# PCIe-SATA.net
KiCad netlist of a schematic drawn in Altium Designer
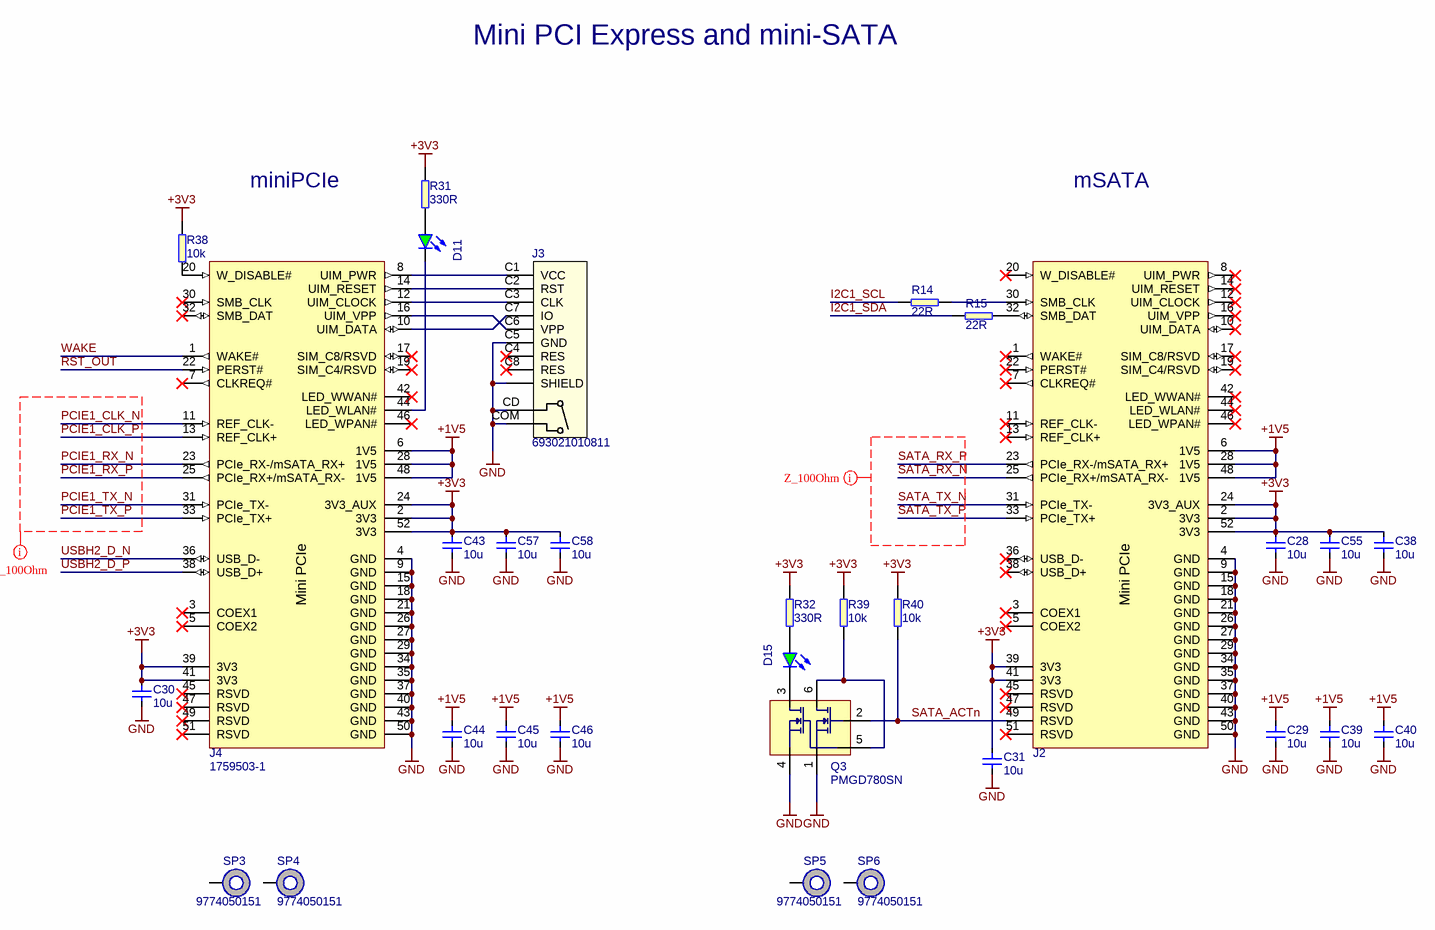
[diagram p0: PCIe-SATA.SchDoc]

(export (version "E")
  (design (tool "Eeschema 10.0.6"))
  (components
    (comp (ref "C28")
      (value "10u")
      (footprint "0603")
      (description "MLCC SMT Capacitor 10uF 0603")
      (fields (field (name "MANUFACTURER") "Walsin") (field (name "PART NUMBER") "C_10u_0603"))
      (libsource (lib "TK1Baseboard") (part "C_10u_0603"))
    )
    (comp (ref "C29")
      (value "10u")
      (footprint "0603")
      (description "MLCC SMT Capacitor 10uF 0603")
      (fields (field (name "MANUFACTURER") "Walsin") (field (name "PART NUMBER") "C_10u_0603"))
      (libsource (lib "TK1Baseboard") (part "C_10u_0603"))
    )
    (comp (ref "C30")
      (value "10u")
      (footprint "0603")
      (description "MLCC SMT Capacitor 10uF 0603")
      (fields (field (name "MANUFACTURER") "Walsin") (field (name "PART NUMBER") "C_10u_0603"))
      (libsource (lib "TK1Baseboard") (part "C_10u_0603"))
    )
    (comp (ref "C31")
      (value "10u")
      (footprint "0603")
      (description "MLCC SMT Capacitor 10uF 0603")
      (fields (field (name "MANUFACTURER") "Walsin") (field (name "PART NUMBER") "C_10u_0603"))
      (libsource (lib "TK1Baseboard") (part "C_10u_0603"))
    )
    (comp (ref "C38")
      (value "10u")
      (footprint "0603")
      (description "MLCC SMT Capacitor 10uF 0603")
      (fields (field (name "MANUFACTURER") "Walsin") (field (name "PART NUMBER") "C_10u_0603"))
      (libsource (lib "TK1Baseboard") (part "C_10u_0603"))
    )
    (comp (ref "C39")
      (value "10u")
      (footprint "0603")
      (description "MLCC SMT Capacitor 10uF 0603")
      (fields (field (name "MANUFACTURER") "Walsin") (field (name "PART NUMBER") "C_10u_0603"))
      (libsource (lib "TK1Baseboard") (part "C_10u_0603"))
    )
    (comp (ref "C40")
      (value "10u")
      (footprint "0603")
      (description "MLCC SMT Capacitor 10uF 0603")
      (fields (field (name "MANUFACTURER") "Walsin") (field (name "PART NUMBER") "C_10u_0603"))
      (libsource (lib "TK1Baseboard") (part "C_10u_0603"))
    )
    (comp (ref "C43")
      (value "10u")
      (footprint "0603")
      (description "MLCC SMT Capacitor 10uF 0603")
      (fields (field (name "MANUFACTURER") "Walsin") (field (name "PART NUMBER") "C_10u_0603"))
      (libsource (lib "TK1Baseboard") (part "C_10u_0603"))
    )
    (comp (ref "C44")
      (value "10u")
      (footprint "0603")
      (description "MLCC SMT Capacitor 10uF 0603")
      (fields (field (name "MANUFACTURER") "Walsin") (field (name "PART NUMBER") "C_10u_0603"))
      (libsource (lib "TK1Baseboard") (part "C_10u_0603"))
    )
    (comp (ref "C45")
      (value "10u")
      (footprint "0603")
      (description "MLCC SMT Capacitor 10uF 0603")
      (fields (field (name "MANUFACTURER") "Walsin") (field (name "PART NUMBER") "C_10u_0603"))
      (libsource (lib "TK1Baseboard") (part "C_10u_0603"))
    )
    (comp (ref "C46")
      (value "10u")
      (footprint "0603")
      (description "MLCC SMT Capacitor 10uF 0603")
      (fields (field (name "MANUFACTURER") "Walsin") (field (name "PART NUMBER") "C_10u_0603"))
      (libsource (lib "TK1Baseboard") (part "C_10u_0603"))
    )
    (comp (ref "C55")
      (value "10u")
      (footprint "0603")
      (description "MLCC SMT Capacitor 10uF 0603")
      (fields (field (name "MANUFACTURER") "Walsin") (field (name "PART NUMBER") "C_10u_0603"))
      (libsource (lib "TK1Baseboard") (part "C_10u_0603"))
    )
    (comp (ref "C57")
      (value "10u")
      (footprint "0603")
      (description "MLCC SMT Capacitor 10uF 0603")
      (fields (field (name "MANUFACTURER") "Walsin") (field (name "PART NUMBER") "C_10u_0603"))
      (libsource (lib "TK1Baseboard") (part "C_10u_0603"))
    )
    (comp (ref "C58")
      (value "10u")
      (footprint "0603")
      (description "MLCC SMT Capacitor 10uF 0603")
      (fields (field (name "MANUFACTURER") "Walsin") (field (name "PART NUMBER") "C_10u_0603"))
      (libsource (lib "TK1Baseboard") (part "C_10u_0603"))
    )
    (comp (ref "D11")
      (value "KPT-1608SGC")
      (footprint "LED0603")
      (description "LED Green 0603 case")
      (fields (field (name "PART NUMBER") "LED_G") (field (name "MANUFACTURER") "KINGBRIGHT"))
      (libsource (lib "TK1Baseboard") (part "LED_G"))
    )
    (comp (ref "D15")
      (value "KPT-1608SGC")
      (footprint "LED0603")
      (description "LED Green 0603 case")
      (fields (field (name "PART NUMBER") "LED_G") (field (name "MANUFACTURER") "KINGBRIGHT"))
      (libsource (lib "TK1Baseboard") (part "LED_G"))
    )
    (comp (ref "J2")
      (value "1759503-1")
      (footprint "1759503-1")
      (description "Mini PCI Express 8mm")
      (fields (field (name "PART NUMBER") "TE-1759503-1") (field (name "MANUFACTURER") "TE CONNECTIVITY"))
      (libsource (lib "TK1Baseboard") (part "MiniPCIExpress"))
    )
    (comp (ref "J3")
      (value "693021010811")
      (footprint "693021010811")
      (description "Micro SIM Card Connector WR-CRD, Push & Push - with Card Detection")
      (fields
        (field (name "MANUFACTURER") "WURTH ELEKTRONIK")
        (field (name "PART NUMBER") "WE-693-021-010-811")
      )
      (libsource (lib "TK1Baseboard") (part "SIM-8P-CD"))
    )
    (comp (ref "J4")
      (value "1759503-1")
      (footprint "1759503-1")
      (description "Mini PCI Express 8mm")
      (fields (field (name "PART NUMBER") "TE-1759503-1") (field (name "MANUFACTURER") "TE CONNECTIVITY"))
      (libsource (lib "TK1Baseboard") (part "MiniPCIExpress"))
    )
    (comp (ref "Q3")
      (value "PMGD780SN")
      (footprint "SOT-363")
      (description "60 V, dual N-channel Trench MOSFET")
      (fields (field (name "MANUFACTURER") "NXP") (field (name "MPN") "PMGD780SN,115"))
      (libsource (lib "TK1Baseboard") (part "PMGD780SN"))
    )
    (comp (ref "R14")
      (value "22R")
      (footprint "0402")
      (description "RES, 22R, 0402")
      (fields (field (name "MANUFACTURER") "VISHAY") (field (name "PART NUMBER") "R_22R_0402"))
      (libsource (lib "TK1Baseboard") (part "R_22R_0402"))
    )
    (comp (ref "R15")
      (value "22R")
      (footprint "0402")
      (description "RES, 22R, 0402")
      (fields (field (name "MANUFACTURER") "VISHAY") (field (name "PART NUMBER") "R_22R_0402"))
      (libsource (lib "TK1Baseboard") (part "R_22R_0402"))
    )
    (comp (ref "R31")
      (value "330R")
      (footprint "0402")
      (description "RES, 330R, 0402")
      (fields (field (name "MANUFACTURER") "MULTICOMP") (field (name "PART NUMBER") "R_330R_0402"))
      (libsource (lib "TK1Baseboard") (part "R_330R_0402"))
    )
    (comp (ref "R32")
      (value "330R")
      (footprint "0402")
      (description "RES, 330R, 0402")
      (fields (field (name "MANUFACTURER") "MULTICOMP") (field (name "PART NUMBER") "R_330R_0402"))
      (libsource (lib "TK1Baseboard") (part "R_330R_0402"))
    )
    (comp (ref "R38")
      (value "10k")
      (footprint "0402")
      (description "RES, 10k, 0402")
      (fields (field (name "MANUFACTURER") "MULTICOMP") (field (name "PART NUMBER") "R_10k_0402"))
      (libsource (lib "TK1Baseboard") (part "R_10k_0402"))
    )
    (comp (ref "R39")
      (value "10k")
      (footprint "0402")
      (description "RES, 10k, 0402")
      (fields (field (name "MANUFACTURER") "MULTICOMP") (field (name "PART NUMBER") "R_10k_0402"))
      (libsource (lib "TK1Baseboard") (part "R_10k_0402"))
    )
    (comp (ref "R40")
      (value "10k")
      (footprint "0402")
      (description "RES, 10k, 0402")
      (fields (field (name "MANUFACTURER") "MULTICOMP") (field (name "PART NUMBER") "R_10k_0402"))
      (libsource (lib "TK1Baseboard") (part "R_10k_0402"))
    )
    (comp (ref "SP3")
      (value "9774050151")
      (footprint "M2.5-5mm")
      (description "M2.5x5")
      (fields (field (name "MANUFACTURER") "WURTH ELEKTRONIK"))
      (libsource (lib "TK1Baseboard") (part "M2.5x5"))
    )
    (comp (ref "SP4")
      (value "9774050151")
      (footprint "M2.5-5mm")
      (description "M2.5x5")
      (fields (field (name "MANUFACTURER") "WURTH ELEKTRONIK"))
      (libsource (lib "TK1Baseboard") (part "M2.5x5"))
    )
    (comp (ref "SP5")
      (value "9774050151")
      (footprint "M2.5-5mm")
      (description "M2.5x5")
      (fields (field (name "MANUFACTURER") "WURTH ELEKTRONIK"))
      (libsource (lib "TK1Baseboard") (part "M2.5x5"))
    )
    (comp (ref "SP6")
      (value "9774050151")
      (footprint "M2.5-5mm")
      (description "M2.5x5")
      (fields (field (name "MANUFACTURER") "WURTH ELEKTRONIK"))
      (libsource (lib "TK1Baseboard") (part "M2.5x5"))
    )
  )
  (nets
    (net (code "1") (name "+1V5") (class "Default")
      (node (ref "C29") (pin "1") (pinfunction "1_1") (pintype "passive"))
      (node (ref "C39") (pin "1") (pinfunction "1_1") (pintype "passive"))
      (node (ref "C40") (pin "1") (pinfunction "1_1") (pintype "passive"))
      (node (ref "C44") (pin "1") (pinfunction "1_1") (pintype "passive"))
      (node (ref "C45") (pin "1") (pinfunction "1_1") (pintype "passive"))
      (node (ref "C46") (pin "1") (pinfunction "1_1") (pintype "passive"))
      (node (ref "J2") (pin "28") (pinfunction "1V5_28") (pintype "power_in"))
      (node (ref "J2") (pin "48") (pinfunction "1V5_48") (pintype "power_in"))
      (node (ref "J2") (pin "6") (pinfunction "1V5_6") (pintype "power_in"))
      (node (ref "J4") (pin "28") (pinfunction "1V5_28") (pintype "power_in"))
      (node (ref "J4") (pin "48") (pinfunction "1V5_48") (pintype "power_in"))
      (node (ref "J4") (pin "6") (pinfunction "1V5_6") (pintype "power_in"))
    )
    (net (code "2") (name "+3V3") (class "Default")
      (node (ref "C28") (pin "1") (pinfunction "1_1") (pintype "passive"))
      (node (ref "C30") (pin "1") (pinfunction "1_1") (pintype "passive"))
      (node (ref "C31") (pin "1") (pinfunction "1_1") (pintype "passive"))
      (node (ref "C38") (pin "1") (pinfunction "1_1") (pintype "passive"))
      (node (ref "C43") (pin "1") (pinfunction "1_1") (pintype "passive"))
      (node (ref "C55") (pin "1") (pinfunction "1_1") (pintype "passive"))
      (node (ref "C57") (pin "1") (pinfunction "1_1") (pintype "passive"))
      (node (ref "C58") (pin "1") (pinfunction "1_1") (pintype "passive"))
      (node (ref "J2") (pin "2") (pinfunction "3V3_2") (pintype "power_in"))
      (node (ref "J2") (pin "24") (pinfunction "3V3_AUX_24") (pintype "power_in"))
      (node (ref "J2") (pin "39") (pinfunction "3V3_39") (pintype "passive"))
      (node (ref "J2") (pin "41") (pinfunction "3V3_41") (pintype "passive"))
      (node (ref "J2") (pin "52") (pinfunction "3V3_52") (pintype "power_in"))
      (node (ref "J4") (pin "2") (pinfunction "3V3_2") (pintype "power_in"))
      (node (ref "J4") (pin "24") (pinfunction "3V3_AUX_24") (pintype "power_in"))
      (node (ref "J4") (pin "39") (pinfunction "3V3_39") (pintype "passive"))
      (node (ref "J4") (pin "41") (pinfunction "3V3_41") (pintype "passive"))
      (node (ref "J4") (pin "52") (pinfunction "3V3_52") (pintype "power_in"))
      (node (ref "R31") (pin "2") (pintype "passive"))
      (node (ref "R32") (pin "2") (pintype "passive"))
      (node (ref "R38") (pin "2") (pintype "passive"))
      (node (ref "R39") (pin "2") (pintype "passive"))
      (node (ref "R40") (pin "2") (pintype "passive"))
    )
    (net (code "3") (name "/I2C1_SCL") (class "Default") (node (ref "R14") (pin "1") (pintype "passive")))
    (net (code "4") (name "/I2C1_SDA") (class "Default") (node (ref "R15") (pin "1") (pintype "passive")))
    (net (code "5") (name "/PCIE1_CLK_N") (class "Default")
      (node (ref "J4") (pin "11") (pinfunction "REF_CLK-_11") (pintype "input"))
    )
    (net (code "6") (name "/PCIE1_CLK_P") (class "Default")
      (node (ref "J4") (pin "13") (pinfunction "REF_CLK+_13") (pintype "input"))
    )
    (net (code "7") (name "/PCIE1_RX_N") (class "Default")
      (node (ref "J4") (pin "23") (pinfunction "PCIe_RX-/mSATA_RX+_23") (pintype "output"))
    )
    (net (code "8") (name "/PCIE1_RX_P") (class "Default")
      (node (ref "J4") (pin "25") (pinfunction "PCIe_RX+/mSATA_RX-_25") (pintype "output"))
    )
    (net (code "9") (name "/PCIE1_TX_N") (class "Default")
      (node (ref "J4") (pin "31") (pinfunction "PCIe_TX-_31") (pintype "input"))
    )
    (net (code "10") (name "/PCIE1_TX_P") (class "Default")
      (node (ref "J4") (pin "33") (pinfunction "PCIe_TX+_33") (pintype "input"))
    )
    (net (code "11") (name "/RST_OUT") (class "Default")
      (node (ref "J4") (pin "22") (pinfunction "PERST#_22") (pintype "input"))
    )
    (net (code "12") (name "/SATA_ACTn") (class "Default")
      (node (ref "J2") (pin "49") (pinfunction "RSVD_49") (pintype "passive"))
      (node (ref "Q3") (pin "2") (pinfunction "G1_2") (pintype "passive"))
      (node (ref "R40") (pin "1") (pintype "passive"))
    )
    (net (code "13") (name "/SATA_RX_N") (class "Default")
      (node (ref "J2") (pin "25") (pinfunction "PCIe_RX+/mSATA_RX-_25") (pintype "output"))
    )
    (net (code "14") (name "/SATA_RX_P") (class "Default")
      (node (ref "J2") (pin "23") (pinfunction "PCIe_RX-/mSATA_RX+_23") (pintype "output"))
    )
    (net (code "15") (name "/SATA_TX_N") (class "Default")
      (node (ref "J2") (pin "31") (pinfunction "PCIe_TX-_31") (pintype "input"))
    )
    (net (code "16") (name "/SATA_TX_P") (class "Default")
      (node (ref "J2") (pin "33") (pinfunction "PCIe_TX+_33") (pintype "input"))
    )
    (net (code "17") (name "/USBH2_D_N") (class "Default")
      (node (ref "J4") (pin "36") (pinfunction "USB_D-_36") (pintype "bidirectional"))
    )
    (net (code "18") (name "/USBH2_D_P") (class "Default")
      (node (ref "J4") (pin "38") (pinfunction "USB_D+_38") (pintype "bidirectional"))
    )
    (net (code "19") (name "/WAKE") (class "Default")
      (node (ref "J4") (pin "1") (pinfunction "WAKE#_1") (pintype "output"))
    )
    (net (code "20") (name "GND") (class "Default")
      (node (ref "C28") (pin "2") (pinfunction "2_2") (pintype "passive"))
      (node (ref "C29") (pin "2") (pinfunction "2_2") (pintype "passive"))
      (node (ref "C30") (pin "2") (pinfunction "2_2") (pintype "passive"))
      (node (ref "C31") (pin "2") (pinfunction "2_2") (pintype "passive"))
      (node (ref "C38") (pin "2") (pinfunction "2_2") (pintype "passive"))
      (node (ref "C39") (pin "2") (pinfunction "2_2") (pintype "passive"))
      (node (ref "C40") (pin "2") (pinfunction "2_2") (pintype "passive"))
      (node (ref "C43") (pin "2") (pinfunction "2_2") (pintype "passive"))
      (node (ref "C44") (pin "2") (pinfunction "2_2") (pintype "passive"))
      (node (ref "C45") (pin "2") (pinfunction "2_2") (pintype "passive"))
      (node (ref "C46") (pin "2") (pinfunction "2_2") (pintype "passive"))
      (node (ref "C55") (pin "2") (pinfunction "2_2") (pintype "passive"))
      (node (ref "C57") (pin "2") (pinfunction "2_2") (pintype "passive"))
      (node (ref "C58") (pin "2") (pinfunction "2_2") (pintype "passive"))
      (node (ref "J2") (pin "15") (pinfunction "GND_15") (pintype "power_in"))
      (node (ref "J2") (pin "18") (pinfunction "GND_18") (pintype "power_in"))
      (node (ref "J2") (pin "21") (pinfunction "GND_21") (pintype "power_in"))
      (node (ref "J2") (pin "26") (pinfunction "GND_26") (pintype "power_in"))
      (node (ref "J2") (pin "27") (pinfunction "GND_27") (pintype "power_in"))
      (node (ref "J2") (pin "29") (pinfunction "GND_29") (pintype "power_in"))
      (node (ref "J2") (pin "34") (pinfunction "GND_34") (pintype "power_in"))
      (node (ref "J2") (pin "35") (pinfunction "GND_35") (pintype "power_in"))
      (node (ref "J2") (pin "37") (pinfunction "GND_37") (pintype "power_in"))
      (node (ref "J2") (pin "4") (pinfunction "GND_4") (pintype "power_in"))
      (node (ref "J2") (pin "40") (pinfunction "GND_40") (pintype "power_in"))
      (node (ref "J2") (pin "43") (pinfunction "GND_43") (pintype "power_in"))
      (node (ref "J2") (pin "50") (pinfunction "GND_50") (pintype "power_in"))
      (node (ref "J2") (pin "9") (pinfunction "GND_9") (pintype "power_in"))
      (node (ref "J3") (pin "C5") (pinfunction "GND_C5") (pintype "passive"))
      (node (ref "J3") (pin "CD") (pinfunction "CD_CD") (pintype "passive"))
      (node (ref "J3") (pin "COM") (pinfunction "COM_COM") (pintype "passive"))
      (node (ref "J3") (pin "SHIELD") (pinfunction "SHIELD_SHIELD") (pintype "passive"))
      (node (ref "J4") (pin "15") (pinfunction "GND_15") (pintype "power_in"))
      (node (ref "J4") (pin "18") (pinfunction "GND_18") (pintype "power_in"))
      (node (ref "J4") (pin "21") (pinfunction "GND_21") (pintype "power_in"))
      (node (ref "J4") (pin "26") (pinfunction "GND_26") (pintype "power_in"))
      (node (ref "J4") (pin "27") (pinfunction "GND_27") (pintype "power_in"))
      (node (ref "J4") (pin "29") (pinfunction "GND_29") (pintype "power_in"))
      (node (ref "J4") (pin "34") (pinfunction "GND_34") (pintype "power_in"))
      (node (ref "J4") (pin "35") (pinfunction "GND_35") (pintype "power_in"))
      (node (ref "J4") (pin "37") (pinfunction "GND_37") (pintype "power_in"))
      (node (ref "J4") (pin "4") (pinfunction "GND_4") (pintype "power_in"))
      (node (ref "J4") (pin "40") (pinfunction "GND_40") (pintype "power_in"))
      (node (ref "J4") (pin "43") (pinfunction "GND_43") (pintype "power_in"))
      (node (ref "J4") (pin "50") (pinfunction "GND_50") (pintype "power_in"))
      (node (ref "J4") (pin "9") (pinfunction "GND_9") (pintype "power_in"))
      (node (ref "Q3") (pin "1") (pinfunction "S1_1") (pintype "passive"))
      (node (ref "Q3") (pin "4") (pinfunction "S2_4") (pintype "passive"))
    )
    (net (code "21") (name "Net-(D11-PadA)") (class "Default")
      (node (ref "D11") (pin "A") (pinfunction "A_A") (pintype "passive"))
      (node (ref "R31") (pin "1") (pintype "passive"))
    )
    (net (code "22") (name "Net-(D15-PadA)") (class "Default")
      (node (ref "D15") (pin "A") (pinfunction "A_A") (pintype "passive"))
      (node (ref "R32") (pin "1") (pintype "passive"))
    )
    (net (code "23") (name "Net-(J2-SMB_CLK)") (class "Default")
      (node (ref "J2") (pin "30") (pinfunction "SMB_CLK_30") (pintype "input"))
      (node (ref "R14") (pin "2") (pintype "passive"))
    )
    (net (code "24") (name "Net-(J2-SMB_DAT)") (class "Default")
      (node (ref "J2") (pin "32") (pinfunction "SMB_DAT_32") (pintype "bidirectional"))
      (node (ref "R15") (pin "2") (pintype "passive"))
    )
    (net (code "25") (name "Net-(J3-CLK)") (class "Default")
      (node (ref "J3") (pin "C3") (pinfunction "CLK_C3") (pintype "passive"))
      (node (ref "J4") (pin "12") (pinfunction "UIM_CLOCK_12") (pintype "output"))
    )
    (net (code "26") (name "Net-(J3-IO)") (class "Default")
      (node (ref "J3") (pin "C7") (pinfunction "IO_C7") (pintype "passive"))
      (node (ref "J4") (pin "10") (pinfunction "UIM_DATA_10") (pintype "bidirectional"))
    )
    (net (code "27") (name "Net-(J3-RST)") (class "Default")
      (node (ref "J3") (pin "C2") (pinfunction "RST_C2") (pintype "passive"))
      (node (ref "J4") (pin "14") (pinfunction "UIM_RESET_14") (pintype "output"))
    )
    (net (code "28") (name "Net-(J3-VCC)") (class "Default")
      (node (ref "J3") (pin "C1") (pinfunction "VCC_C1") (pintype "passive"))
      (node (ref "J4") (pin "8") (pinfunction "UIM_PWR_8") (pintype "output"))
    )
    (net (code "29") (name "Net-(J3-VPP)") (class "Default")
      (node (ref "J3") (pin "C6") (pinfunction "VPP_C6") (pintype "passive"))
      (node (ref "J4") (pin "16") (pinfunction "UIM_VPP_16") (pintype "output"))
    )
    (net (code "30") (name "Net-(J4-LED_WLAN#)") (class "Default")
      (node (ref "D11") (pin "K") (pinfunction "K_K") (pintype "passive"))
      (node (ref "J4") (pin "44") (pinfunction "LED_WLAN#_44") (pintype "open_collector"))
    )
    (net (code "31") (name "Net-(J4-W_DISABLE#)") (class "Default")
      (node (ref "J4") (pin "20") (pinfunction "W_DISABLE#_20") (pintype "input"))
      (node (ref "R38") (pin "1") (pintype "passive"))
    )
    (net (code "32") (name "Net-(Q3-D1)") (class "Default")
      (node (ref "Q3") (pin "5") (pinfunction "G2_5") (pintype "passive"))
      (node (ref "Q3") (pin "6") (pinfunction "D1_6") (pintype "passive"))
      (node (ref "R39") (pin "1") (pintype "passive"))
    )
    (net (code "33") (name "Net-(Q3-D2)") (class "Default")
      (node (ref "D15") (pin "K") (pinfunction "K_K") (pintype "passive"))
      (node (ref "Q3") (pin "3") (pinfunction "D2_3") (pintype "passive"))
    )
    (net (code "34") (name "unconnected-(J2-CLKREQ#-Pad7)") (class "Default")
      (node (ref "J2") (pin "7") (pinfunction "CLKREQ#_7") (pintype "output+no_connect"))
    )
    (net (code "35") (name "unconnected-(J2-COEX1-Pad3)") (class "Default")
      (node (ref "J2") (pin "3") (pinfunction "COEX1_3") (pintype "passive+no_connect"))
    )
    (net (code "36") (name "unconnected-(J2-COEX2-Pad5)") (class "Default")
      (node (ref "J2") (pin "5") (pinfunction "COEX2_5") (pintype "passive+no_connect"))
    )
    (net (code "37") (name "unconnected-(J2-LED_WLAN#-Pad44)") (class "Default")
      (node (ref "J2") (pin "44") (pinfunction "LED_WLAN#_44") (pintype "open_collector+no_connect"))
    )
    (net (code "38") (name "unconnected-(J2-LED_WPAN#-Pad46)") (class "Default")
      (node (ref "J2") (pin "46") (pinfunction "LED_WPAN#_46") (pintype "open_collector+no_connect"))
    )
    (net (code "39") (name "unconnected-(J2-LED_WWAN#-Pad42)") (class "Default")
      (node (ref "J2") (pin "42") (pinfunction "LED_WWAN#_42") (pintype "open_collector+no_connect"))
    )
    (net (code "40") (name "unconnected-(J2-PERST#-Pad22)") (class "Default")
      (node (ref "J2") (pin "22") (pinfunction "PERST#_22") (pintype "input+no_connect"))
    )
    (net (code "41") (name "unconnected-(J2-REF_CLK+-Pad13)") (class "Default")
      (node (ref "J2") (pin "13") (pinfunction "REF_CLK+_13") (pintype "input+no_connect"))
    )
    (net (code "42") (name "unconnected-(J2-REF_CLK--Pad11)") (class "Default")
      (node (ref "J2") (pin "11") (pinfunction "REF_CLK-_11") (pintype "input+no_connect"))
    )
    (net (code "43") (name "unconnected-(J2-RSVD-Pad45)") (class "Default")
      (node (ref "J2") (pin "45") (pinfunction "RSVD_45") (pintype "passive+no_connect"))
    )
    (net (code "44") (name "unconnected-(J2-RSVD-Pad47)") (class "Default")
      (node (ref "J2") (pin "47") (pinfunction "RSVD_47") (pintype "passive+no_connect"))
    )
    (net (code "45") (name "unconnected-(J2-RSVD-Pad51)") (class "Default")
      (node (ref "J2") (pin "51") (pinfunction "RSVD_51") (pintype "passive+no_connect"))
    )
    (net (code "46") (name "unconnected-(J2-SIM_C4{slash}RSVD-Pad19)") (class "Default")
      (node (ref "J2") (pin "19") (pinfunction "SIM_C4/RSVD_19") (pintype "bidirectional+no_connect"))
    )
    (net (code "47") (name "unconnected-(J2-SIM_C8{slash}RSVD-Pad17)") (class "Default")
      (node (ref "J2") (pin "17") (pinfunction "SIM_C8/RSVD_17") (pintype "bidirectional+no_connect"))
    )
    (net (code "48") (name "unconnected-(J2-UIM_CLOCK-Pad12)") (class "Default")
      (node (ref "J2") (pin "12") (pinfunction "UIM_CLOCK_12") (pintype "output+no_connect"))
    )
    (net (code "49") (name "unconnected-(J2-UIM_DATA-Pad10)") (class "Default")
      (node (ref "J2") (pin "10") (pinfunction "UIM_DATA_10") (pintype "bidirectional+no_connect"))
    )
    (net (code "50") (name "unconnected-(J2-UIM_PWR-Pad8)") (class "Default")
      (node (ref "J2") (pin "8") (pinfunction "UIM_PWR_8") (pintype "output+no_connect"))
    )
    (net (code "51") (name "unconnected-(J2-UIM_RESET-Pad14)") (class "Default")
      (node (ref "J2") (pin "14") (pinfunction "UIM_RESET_14") (pintype "output+no_connect"))
    )
    (net (code "52") (name "unconnected-(J2-UIM_VPP-Pad16)") (class "Default")
      (node (ref "J2") (pin "16") (pinfunction "UIM_VPP_16") (pintype "output+no_connect"))
    )
    (net (code "53") (name "unconnected-(J2-USB_D+-Pad38)") (class "Default")
      (node (ref "J2") (pin "38") (pinfunction "USB_D+_38") (pintype "bidirectional+no_connect"))
    )
    (net (code "54") (name "unconnected-(J2-USB_D--Pad36)") (class "Default")
      (node (ref "J2") (pin "36") (pinfunction "USB_D-_36") (pintype "bidirectional+no_connect"))
    )
    (net (code "55") (name "unconnected-(J2-WAKE#-Pad1)") (class "Default")
      (node (ref "J2") (pin "1") (pinfunction "WAKE#_1") (pintype "output+no_connect"))
    )
    (net (code "56") (name "unconnected-(J2-W_DISABLE#-Pad20)") (class "Default")
      (node (ref "J2") (pin "20") (pinfunction "W_DISABLE#_20") (pintype "input+no_connect"))
    )
    (net (code "57") (name "unconnected-(J3-RES-PadC4)") (class "Default")
      (node (ref "J3") (pin "C4") (pinfunction "RES_C4") (pintype "passive+no_connect"))
    )
    (net (code "58") (name "unconnected-(J3-RES-PadC8)") (class "Default")
      (node (ref "J3") (pin "C8") (pinfunction "RES_C8") (pintype "passive+no_connect"))
    )
    (net (code "59") (name "unconnected-(J4-CLKREQ#-Pad7)") (class "Default")
      (node (ref "J4") (pin "7") (pinfunction "CLKREQ#_7") (pintype "output+no_connect"))
    )
    (net (code "60") (name "unconnected-(J4-COEX1-Pad3)") (class "Default")
      (node (ref "J4") (pin "3") (pinfunction "COEX1_3") (pintype "passive+no_connect"))
    )
    (net (code "61") (name "unconnected-(J4-COEX2-Pad5)") (class "Default")
      (node (ref "J4") (pin "5") (pinfunction "COEX2_5") (pintype "passive+no_connect"))
    )
    (net (code "62") (name "unconnected-(J4-LED_WPAN#-Pad46)") (class "Default")
      (node (ref "J4") (pin "46") (pinfunction "LED_WPAN#_46") (pintype "open_collector+no_connect"))
    )
    (net (code "63") (name "unconnected-(J4-LED_WWAN#-Pad42)") (class "Default")
      (node (ref "J4") (pin "42") (pinfunction "LED_WWAN#_42") (pintype "open_collector+no_connect"))
    )
    (net (code "64") (name "unconnected-(J4-RSVD-Pad45)") (class "Default")
      (node (ref "J4") (pin "45") (pinfunction "RSVD_45") (pintype "passive+no_connect"))
    )
    (net (code "65") (name "unconnected-(J4-RSVD-Pad47)") (class "Default")
      (node (ref "J4") (pin "47") (pinfunction "RSVD_47") (pintype "passive+no_connect"))
    )
    (net (code "66") (name "unconnected-(J4-RSVD-Pad49)") (class "Default")
      (node (ref "J4") (pin "49") (pinfunction "RSVD_49") (pintype "passive+no_connect"))
    )
    (net (code "67") (name "unconnected-(J4-RSVD-Pad51)") (class "Default")
      (node (ref "J4") (pin "51") (pinfunction "RSVD_51") (pintype "passive+no_connect"))
    )
    (net (code "68") (name "unconnected-(J4-SIM_C4{slash}RSVD-Pad19)") (class "Default")
      (node (ref "J4") (pin "19") (pinfunction "SIM_C4/RSVD_19") (pintype "bidirectional+no_connect"))
    )
    (net (code "69") (name "unconnected-(J4-SIM_C8{slash}RSVD-Pad17)") (class "Default")
      (node (ref "J4") (pin "17") (pinfunction "SIM_C8/RSVD_17") (pintype "bidirectional+no_connect"))
    )
    (net (code "70") (name "unconnected-(J4-SMB_CLK-Pad30)") (class "Default")
      (node (ref "J4") (pin "30") (pinfunction "SMB_CLK_30") (pintype "input+no_connect"))
    )
    (net (code "71") (name "unconnected-(J4-SMB_DAT-Pad32)") (class "Default")
      (node (ref "J4") (pin "32") (pinfunction "SMB_DAT_32") (pintype "bidirectional+no_connect"))
    )
    (net (code "72") (name "unconnected-(SP3-Pad1)") (class "Default")
      (node (ref "SP3") (pin "1") (pinfunction "1_1") (pintype "passive"))
    )
    (net (code "73") (name "unconnected-(SP4-Pad1)") (class "Default")
      (node (ref "SP4") (pin "1") (pinfunction "1_1") (pintype "passive"))
    )
    (net (code "74") (name "unconnected-(SP5-Pad1)") (class "Default")
      (node (ref "SP5") (pin "1") (pinfunction "1_1") (pintype "passive"))
    )
    (net (code "75") (name "unconnected-(SP6-Pad1)") (class "Default")
      (node (ref "SP6") (pin "1") (pinfunction "1_1") (pintype "passive"))
    )
  )
)
